# RS485_2.net
KiCad netlist of a schematic drawn in Altium Designer
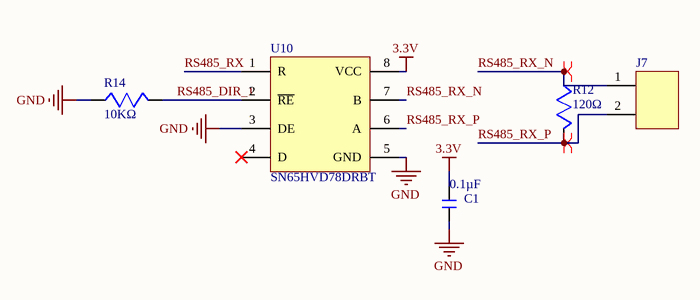
[diagram p0: RS485_2.SchDoc]

(export (version "E")
  (design (tool "Eeschema 10.0.6"))
  (components
    (comp (ref "C1")
      (value "0.1µF")
      (footprint "402 capacitor - duplicate")
      (description "CON SMD 402")
      (fields (field (name "MPN") "CL05A104KA5NNNC") (field (name "Comment") "0402 capacitor"))
      (libsource (lib "Schlib1") (part "CON SMD 402"))
    )
    (comp (ref "J7")
      (value "2 POS")
      (footprint "0901362102")
      (description "CONN HEADER R/A 2POS 2.54MM")
      (fields (field (name "MPN") "0901362102"))
      (libsource (lib "Schlib1") (part "0901362102"))
    )
    (comp (ref "R12")
      (value "120Ω")
      (footprint "402 RESISTOR")
      (description "RES SMD 0402")
      (fields (field (name "MPN") "ERJ-2RKF1200X") (field (name "Comment") "0402. RESİSTOR"))
      (libsource (lib "Schlib1") (part "RES SMD 0402"))
    )
    (comp (ref "R14")
      (value "10KΩ")
      (footprint "402 RESISTOR")
      (description "RES SMD 0402")
      (fields (field (name "MPN") "RNCF0402BTE10K0") (field (name "Comment") "0402. RESİSTOR"))
      (libsource (lib "Schlib1") (part "RES SMD 0402"))
    )
    (comp (ref "U10")
      (value "SN65HVD78DRBT")
      (description "IC TRANSCEIVER HALF 1/1 8SON")
      (libsource (lib "Schlib1") (part "SN65HVD78DRBT"))
    )
  )
  (nets
    (net (code "1") (name "/RS485_DIR_1") (class "Default")
      (node (ref "R14") (pin "2") (pintype "passive"))
      (node (ref "U10") (pin "2") (pinfunction "~{RE}_2") (pintype "passive"))
    )
    (net (code "2") (name "/RS485_RX") (class "Default")
      (node (ref "U10") (pin "1") (pinfunction "R_1") (pintype "passive"))
    )
    (net (code "3") (name "/RS485_RX_N") (class "Default")
      (node (ref "J7") (pin "1") (pintype "passive"))
      (node (ref "R12") (pin "1") (pintype "passive"))
      (node (ref "U10") (pin "7") (pinfunction "B_7") (pintype "passive"))
    )
    (net (code "4") (name "/RS485_RX_P") (class "Default")
      (node (ref "J7") (pin "2") (pintype "passive"))
      (node (ref "R12") (pin "2") (pintype "passive"))
      (node (ref "U10") (pin "6") (pinfunction "A_6") (pintype "passive"))
    )
    (net (code "5") (name "3.3V") (class "Default")
      (node (ref "C1") (pin "2") (pintype "passive"))
      (node (ref "U10") (pin "8") (pinfunction "VCC_8") (pintype "passive"))
    )
    (net (code "6") (name "GND") (class "Default")
      (node (ref "C1") (pin "1") (pintype "passive"))
      (node (ref "R14") (pin "1") (pintype "passive"))
      (node (ref "U10") (pin "3") (pinfunction "DE_3") (pintype "passive"))
      (node (ref "U10") (pin "5") (pinfunction "GND_5") (pintype "passive"))
    )
    (net (code "7") (name "unconnected-(U10-D-Pad4)") (class "Default")
      (node (ref "U10") (pin "4") (pinfunction "D_4") (pintype "passive+no_connect"))
    )
  )
)
